# ppc_ddr2_1.net
KiCad netlist of a schematic drawn in Altium Designer
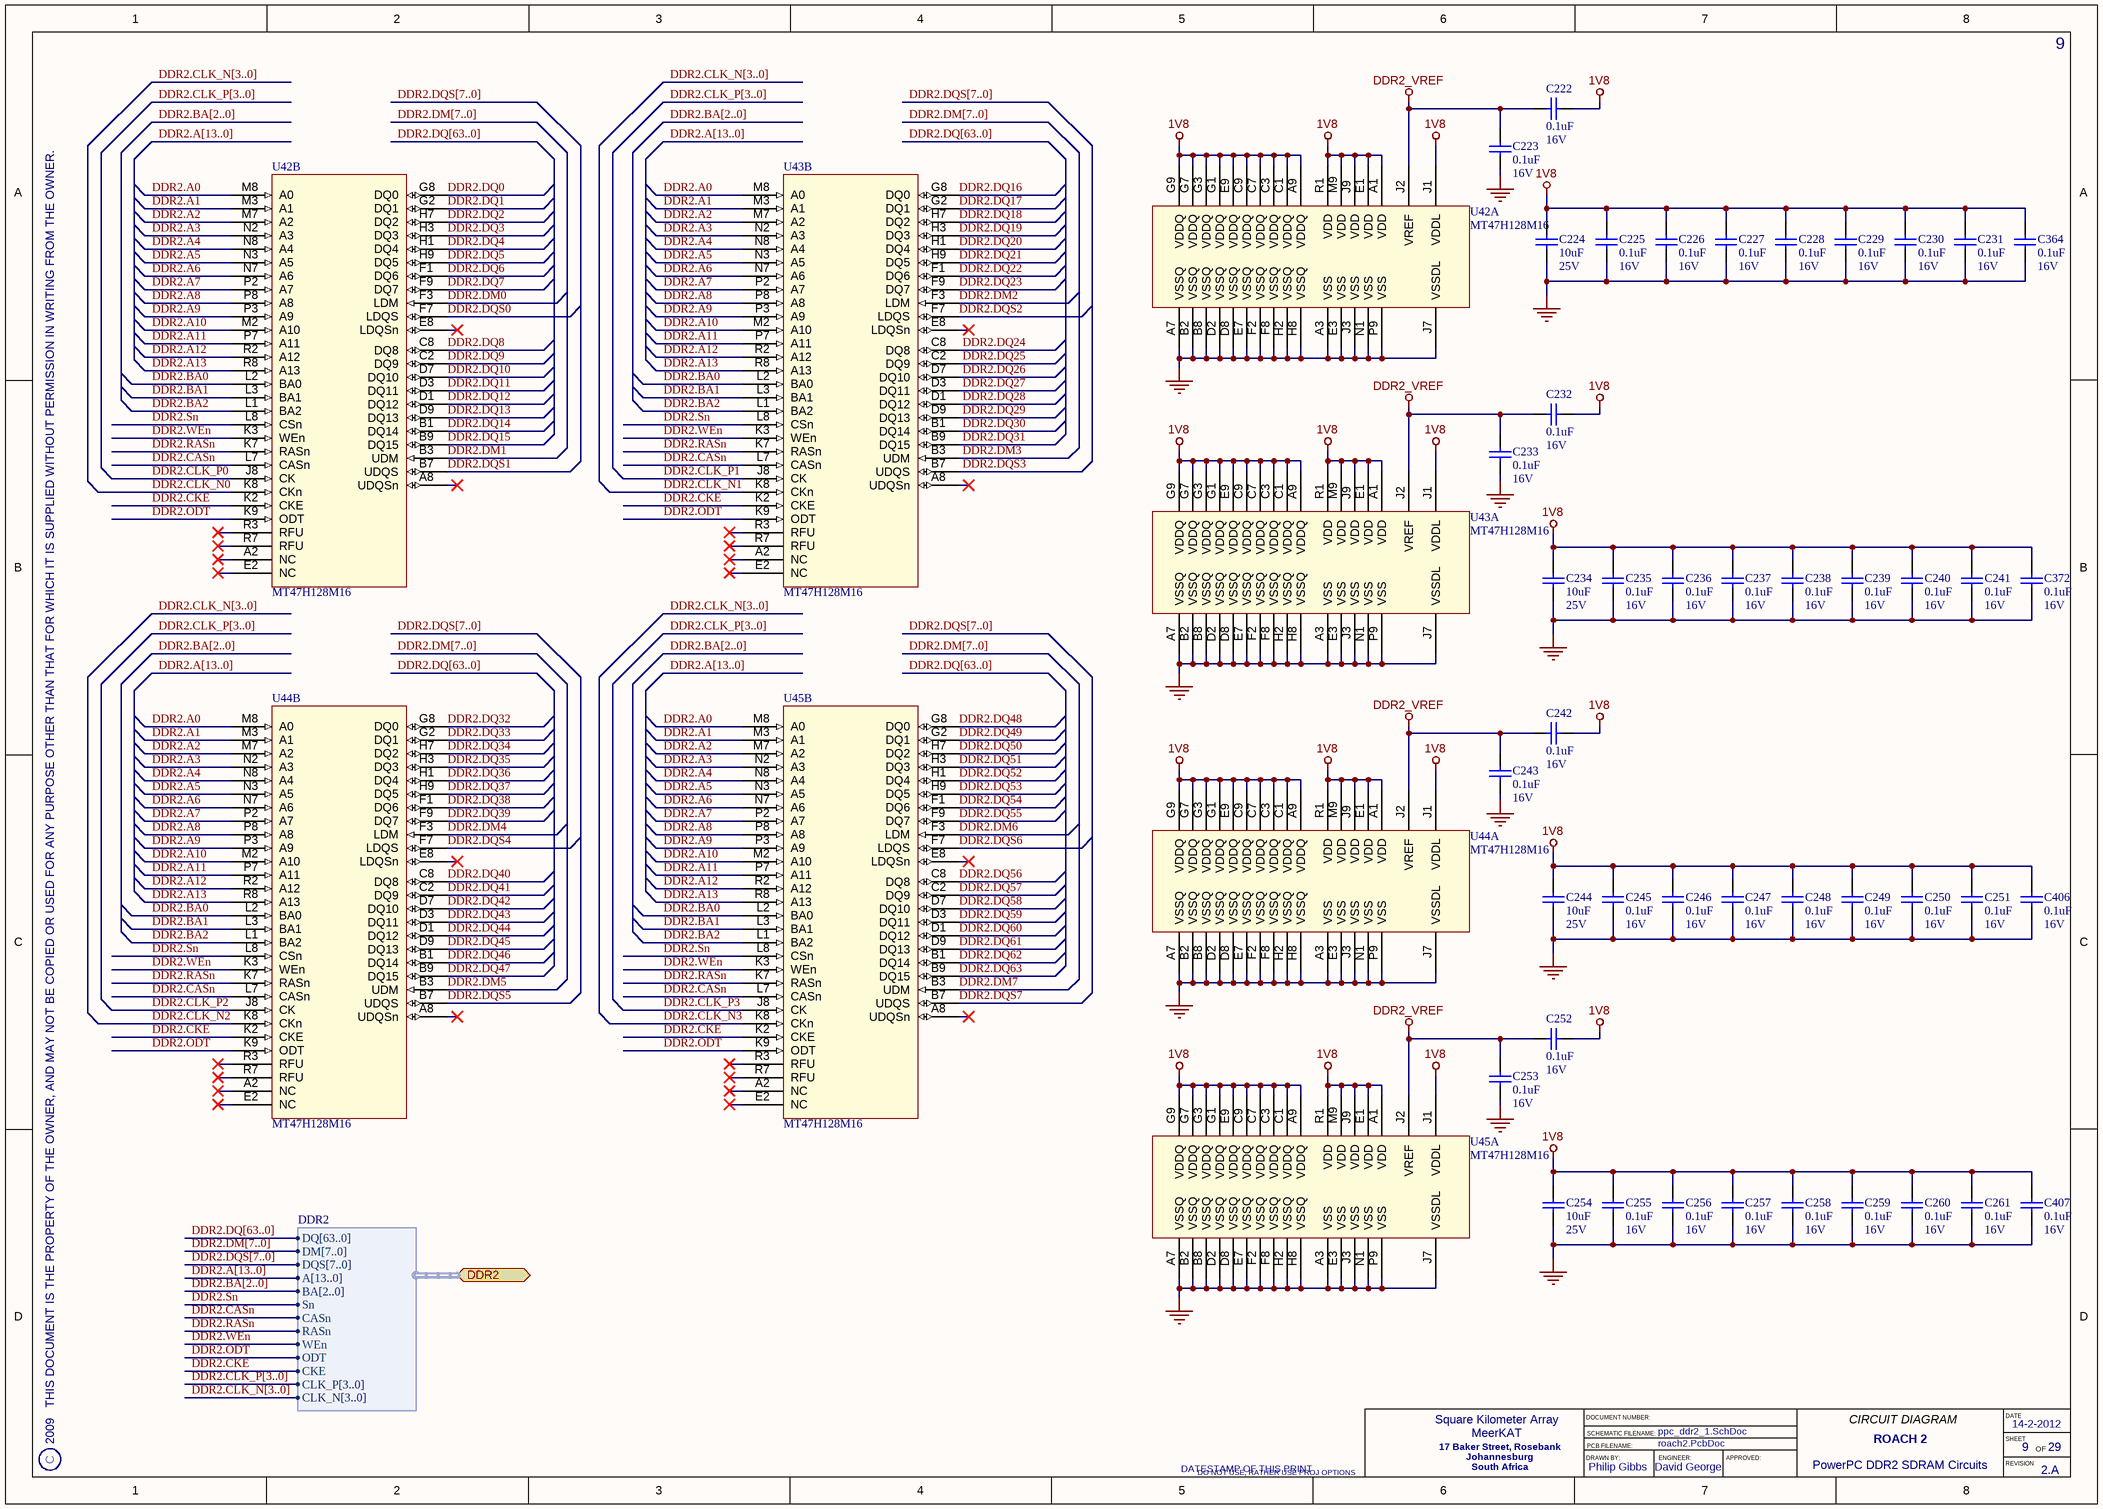
[diagram p0: ppc_ddr2_1.SchDoc]

(export (version "E")
  (design (tool "Eeschema 10.0.6"))
  (components
    (comp (ref "C222")
      (value "0.1uF")
      (footprint "CAPC1005X60L")
      (description "0.1uF, Ceramic Capacitor")
      (fields
        (field (name "RATING") "16V")
        (field (name "MANUFACTURER") "VENKEL")
        (field (name "PARTNUM") "C0402X7R160-104KN")
      )
      (libsource (lib "altium_db") (part "CapStd"))
    )
    (comp (ref "C223")
      (value "0.1uF")
      (footprint "CAPC1005X60L")
      (description "0.1uF, Ceramic Capacitor")
      (fields
        (field (name "RATING") "16V")
        (field (name "MANUFACTURER") "VENKEL")
        (field (name "PARTNUM") "C0402X7R160-104KN")
      )
      (libsource (lib "altium_db") (part "CapStd"))
    )
    (comp (ref "C224")
      (value "10uF")
      (footprint "CAPC3225X200L")
      (description "10uF, Ceramic Capacitor")
      (fields
        (field (name "RATING") "25V")
        (field (name "MANUFACTURER") "MURATA")
        (field (name "PARTNUM") "GRM32DR61E106KA12L")
      )
      (libsource (lib "altium_db") (part "CapStd"))
    )
    (comp (ref "C225")
      (value "0.1uF")
      (footprint "CAPC1005X60L")
      (description "0.1uF, Ceramic Capacitor")
      (fields
        (field (name "RATING") "16V")
        (field (name "MANUFACTURER") "VENKEL")
        (field (name "PARTNUM") "C0402X7R160-104KN")
      )
      (libsource (lib "altium_db") (part "CapStd"))
    )
    (comp (ref "C226")
      (value "0.1uF")
      (footprint "CAPC1005X60L")
      (description "0.1uF, Ceramic Capacitor")
      (fields
        (field (name "RATING") "16V")
        (field (name "MANUFACTURER") "VENKEL")
        (field (name "PARTNUM") "C0402X7R160-104KN")
      )
      (libsource (lib "altium_db") (part "CapStd"))
    )
    (comp (ref "C227")
      (value "0.1uF")
      (footprint "CAPC1005X60L")
      (description "0.1uF, Ceramic Capacitor")
      (fields
        (field (name "RATING") "16V")
        (field (name "MANUFACTURER") "VENKEL")
        (field (name "PARTNUM") "C0402X7R160-104KN")
      )
      (libsource (lib "altium_db") (part "CapStd"))
    )
    (comp (ref "C228")
      (value "0.1uF")
      (footprint "CAPC1005X60L")
      (description "0.1uF, Ceramic Capacitor")
      (fields
        (field (name "RATING") "16V")
        (field (name "MANUFACTURER") "VENKEL")
        (field (name "PARTNUM") "C0402X7R160-104KN")
      )
      (libsource (lib "altium_db") (part "CapStd"))
    )
    (comp (ref "C229")
      (value "0.1uF")
      (footprint "CAPC1005X60L")
      (description "0.1uF, Ceramic Capacitor")
      (fields
        (field (name "RATING") "16V")
        (field (name "MANUFACTURER") "VENKEL")
        (field (name "PARTNUM") "C0402X7R160-104KN")
      )
      (libsource (lib "altium_db") (part "CapStd"))
    )
    (comp (ref "C230")
      (value "0.1uF")
      (footprint "CAPC1005X60L")
      (description "0.1uF, Ceramic Capacitor")
      (fields
        (field (name "RATING") "16V")
        (field (name "MANUFACTURER") "VENKEL")
        (field (name "PARTNUM") "C0402X7R160-104KN")
      )
      (libsource (lib "altium_db") (part "CapStd"))
    )
    (comp (ref "C231")
      (value "0.1uF")
      (footprint "CAPC1005X60L")
      (description "0.1uF, Ceramic Capacitor")
      (fields
        (field (name "RATING") "16V")
        (field (name "MANUFACTURER") "VENKEL")
        (field (name "PARTNUM") "C0402X7R160-104KN")
      )
      (libsource (lib "altium_db") (part "CapStd"))
    )
    (comp (ref "C232")
      (value "0.1uF")
      (footprint "CAPC1005X60L")
      (description "0.1uF, Ceramic Capacitor")
      (fields
        (field (name "RATING") "16V")
        (field (name "MANUFACTURER") "VENKEL")
        (field (name "PARTNUM") "C0402X7R160-104KN")
      )
      (libsource (lib "altium_db") (part "CapStd"))
    )
    (comp (ref "C233")
      (value "0.1uF")
      (footprint "CAPC1005X60L")
      (description "0.1uF, Ceramic Capacitor")
      (fields
        (field (name "RATING") "16V")
        (field (name "MANUFACTURER") "VENKEL")
        (field (name "PARTNUM") "C0402X7R160-104KN")
      )
      (libsource (lib "altium_db") (part "CapStd"))
    )
    (comp (ref "C234")
      (value "10uF")
      (footprint "CAPC3225X200L")
      (description "10uF, Ceramic Capacitor")
      (fields
        (field (name "RATING") "25V")
        (field (name "MANUFACTURER") "MURATA")
        (field (name "PARTNUM") "GRM32DR61E106KA12L")
      )
      (libsource (lib "altium_db") (part "CapStd"))
    )
    (comp (ref "C235")
      (value "0.1uF")
      (footprint "CAPC1005X60L")
      (description "0.1uF, Ceramic Capacitor")
      (fields
        (field (name "RATING") "16V")
        (field (name "MANUFACTURER") "VENKEL")
        (field (name "PARTNUM") "C0402X7R160-104KN")
      )
      (libsource (lib "altium_db") (part "CapStd"))
    )
    (comp (ref "C236")
      (value "0.1uF")
      (footprint "CAPC1005X60L")
      (description "0.1uF, Ceramic Capacitor")
      (fields
        (field (name "RATING") "16V")
        (field (name "MANUFACTURER") "VENKEL")
        (field (name "PARTNUM") "C0402X7R160-104KN")
      )
      (libsource (lib "altium_db") (part "CapStd"))
    )
    (comp (ref "C237")
      (value "0.1uF")
      (footprint "CAPC1005X60L")
      (description "0.1uF, Ceramic Capacitor")
      (fields
        (field (name "RATING") "16V")
        (field (name "MANUFACTURER") "VENKEL")
        (field (name "PARTNUM") "C0402X7R160-104KN")
      )
      (libsource (lib "altium_db") (part "CapStd"))
    )
    (comp (ref "C238")
      (value "0.1uF")
      (footprint "CAPC1005X60L")
      (description "0.1uF, Ceramic Capacitor")
      (fields
        (field (name "RATING") "16V")
        (field (name "MANUFACTURER") "VENKEL")
        (field (name "PARTNUM") "C0402X7R160-104KN")
      )
      (libsource (lib "altium_db") (part "CapStd"))
    )
    (comp (ref "C239")
      (value "0.1uF")
      (footprint "CAPC1005X60L")
      (description "0.1uF, Ceramic Capacitor")
      (fields
        (field (name "RATING") "16V")
        (field (name "MANUFACTURER") "VENKEL")
        (field (name "PARTNUM") "C0402X7R160-104KN")
      )
      (libsource (lib "altium_db") (part "CapStd"))
    )
    (comp (ref "C240")
      (value "0.1uF")
      (footprint "CAPC1005X60L")
      (description "0.1uF, Ceramic Capacitor")
      (fields
        (field (name "RATING") "16V")
        (field (name "MANUFACTURER") "VENKEL")
        (field (name "PARTNUM") "C0402X7R160-104KN")
      )
      (libsource (lib "altium_db") (part "CapStd"))
    )
    (comp (ref "C241")
      (value "0.1uF")
      (footprint "CAPC1005X60L")
      (description "0.1uF, Ceramic Capacitor")
      (fields
        (field (name "RATING") "16V")
        (field (name "MANUFACTURER") "VENKEL")
        (field (name "PARTNUM") "C0402X7R160-104KN")
      )
      (libsource (lib "altium_db") (part "CapStd"))
    )
    (comp (ref "C242")
      (value "0.1uF")
      (footprint "CAPC1005X60L")
      (description "0.1uF, Ceramic Capacitor")
      (fields
        (field (name "RATING") "16V")
        (field (name "MANUFACTURER") "VENKEL")
        (field (name "PARTNUM") "C0402X7R160-104KN")
      )
      (libsource (lib "altium_db") (part "CapStd"))
    )
    (comp (ref "C243")
      (value "0.1uF")
      (footprint "CAPC1005X60L")
      (description "0.1uF, Ceramic Capacitor")
      (fields
        (field (name "RATING") "16V")
        (field (name "MANUFACTURER") "VENKEL")
        (field (name "PARTNUM") "C0402X7R160-104KN")
      )
      (libsource (lib "altium_db") (part "CapStd"))
    )
    (comp (ref "C244")
      (value "10uF")
      (footprint "CAPC3225X200L")
      (description "10uF, Ceramic Capacitor")
      (fields
        (field (name "RATING") "25V")
        (field (name "MANUFACTURER") "MURATA")
        (field (name "PARTNUM") "GRM32DR61E106KA12L")
      )
      (libsource (lib "altium_db") (part "CapStd"))
    )
    (comp (ref "C245")
      (value "0.1uF")
      (footprint "CAPC1005X60L")
      (description "0.1uF, Ceramic Capacitor")
      (fields
        (field (name "RATING") "16V")
        (field (name "MANUFACTURER") "VENKEL")
        (field (name "PARTNUM") "C0402X7R160-104KN")
      )
      (libsource (lib "altium_db") (part "CapStd"))
    )
    (comp (ref "C246")
      (value "0.1uF")
      (footprint "CAPC1005X60L")
      (description "0.1uF, Ceramic Capacitor")
      (fields
        (field (name "RATING") "16V")
        (field (name "MANUFACTURER") "VENKEL")
        (field (name "PARTNUM") "C0402X7R160-104KN")
      )
      (libsource (lib "altium_db") (part "CapStd"))
    )
    (comp (ref "C247")
      (value "0.1uF")
      (footprint "CAPC1005X60L")
      (description "0.1uF, Ceramic Capacitor")
      (fields
        (field (name "RATING") "16V")
        (field (name "MANUFACTURER") "VENKEL")
        (field (name "PARTNUM") "C0402X7R160-104KN")
      )
      (libsource (lib "altium_db") (part "CapStd"))
    )
    (comp (ref "C248")
      (value "0.1uF")
      (footprint "CAPC1005X60L")
      (description "0.1uF, Ceramic Capacitor")
      (fields
        (field (name "RATING") "16V")
        (field (name "MANUFACTURER") "VENKEL")
        (field (name "PARTNUM") "C0402X7R160-104KN")
      )
      (libsource (lib "altium_db") (part "CapStd"))
    )
    (comp (ref "C249")
      (value "0.1uF")
      (footprint "CAPC1005X60L")
      (description "0.1uF, Ceramic Capacitor")
      (fields
        (field (name "RATING") "16V")
        (field (name "MANUFACTURER") "VENKEL")
        (field (name "PARTNUM") "C0402X7R160-104KN")
      )
      (libsource (lib "altium_db") (part "CapStd"))
    )
    (comp (ref "C250")
      (value "0.1uF")
      (footprint "CAPC1005X60L")
      (description "0.1uF, Ceramic Capacitor")
      (fields
        (field (name "RATING") "16V")
        (field (name "MANUFACTURER") "VENKEL")
        (field (name "PARTNUM") "C0402X7R160-104KN")
      )
      (libsource (lib "altium_db") (part "CapStd"))
    )
    (comp (ref "C251")
      (value "0.1uF")
      (footprint "CAPC1005X60L")
      (description "0.1uF, Ceramic Capacitor")
      (fields
        (field (name "RATING") "16V")
        (field (name "MANUFACTURER") "VENKEL")
        (field (name "PARTNUM") "C0402X7R160-104KN")
      )
      (libsource (lib "altium_db") (part "CapStd"))
    )
    (comp (ref "C252")
      (value "0.1uF")
      (footprint "CAPC1005X60L")
      (description "0.1uF, Ceramic Capacitor")
      (fields
        (field (name "RATING") "16V")
        (field (name "MANUFACTURER") "VENKEL")
        (field (name "PARTNUM") "C0402X7R160-104KN")
      )
      (libsource (lib "altium_db") (part "CapStd"))
    )
    (comp (ref "C253")
      (value "0.1uF")
      (footprint "CAPC1005X60L")
      (description "0.1uF, Ceramic Capacitor")
      (fields
        (field (name "RATING") "16V")
        (field (name "MANUFACTURER") "VENKEL")
        (field (name "PARTNUM") "C0402X7R160-104KN")
      )
      (libsource (lib "altium_db") (part "CapStd"))
    )
    (comp (ref "C254")
      (value "10uF")
      (footprint "CAPC3225X200L")
      (description "10uF, Ceramic Capacitor")
      (fields
        (field (name "RATING") "25V")
        (field (name "MANUFACTURER") "MURATA")
        (field (name "PARTNUM") "GRM32DR61E106KA12L")
      )
      (libsource (lib "altium_db") (part "CapStd"))
    )
    (comp (ref "C255")
      (value "0.1uF")
      (footprint "CAPC1005X60L")
      (description "0.1uF, Ceramic Capacitor")
      (fields
        (field (name "RATING") "16V")
        (field (name "MANUFACTURER") "VENKEL")
        (field (name "PARTNUM") "C0402X7R160-104KN")
      )
      (libsource (lib "altium_db") (part "CapStd"))
    )
    (comp (ref "C256")
      (value "0.1uF")
      (footprint "CAPC1005X60L")
      (description "0.1uF, Ceramic Capacitor")
      (fields
        (field (name "RATING") "16V")
        (field (name "MANUFACTURER") "VENKEL")
        (field (name "PARTNUM") "C0402X7R160-104KN")
      )
      (libsource (lib "altium_db") (part "CapStd"))
    )
    (comp (ref "C257")
      (value "0.1uF")
      (footprint "CAPC1005X60L")
      (description "0.1uF, Ceramic Capacitor")
      (fields
        (field (name "RATING") "16V")
        (field (name "MANUFACTURER") "VENKEL")
        (field (name "PARTNUM") "C0402X7R160-104KN")
      )
      (libsource (lib "altium_db") (part "CapStd"))
    )
    (comp (ref "C258")
      (value "0.1uF")
      (footprint "CAPC1005X60L")
      (description "0.1uF, Ceramic Capacitor")
      (fields
        (field (name "RATING") "16V")
        (field (name "MANUFACTURER") "VENKEL")
        (field (name "PARTNUM") "C0402X7R160-104KN")
      )
      (libsource (lib "altium_db") (part "CapStd"))
    )
    (comp (ref "C259")
      (value "0.1uF")
      (footprint "CAPC1005X60L")
      (description "0.1uF, Ceramic Capacitor")
      (fields
        (field (name "RATING") "16V")
        (field (name "MANUFACTURER") "VENKEL")
        (field (name "PARTNUM") "C0402X7R160-104KN")
      )
      (libsource (lib "altium_db") (part "CapStd"))
    )
    (comp (ref "C260")
      (value "0.1uF")
      (footprint "CAPC1005X60L")
      (description "0.1uF, Ceramic Capacitor")
      (fields
        (field (name "RATING") "16V")
        (field (name "MANUFACTURER") "VENKEL")
        (field (name "PARTNUM") "C0402X7R160-104KN")
      )
      (libsource (lib "altium_db") (part "CapStd"))
    )
    (comp (ref "C261")
      (value "0.1uF")
      (footprint "CAPC1005X60L")
      (description "0.1uF, Ceramic Capacitor")
      (fields
        (field (name "RATING") "16V")
        (field (name "MANUFACTURER") "VENKEL")
        (field (name "PARTNUM") "C0402X7R160-104KN")
      )
      (libsource (lib "altium_db") (part "CapStd"))
    )
    (comp (ref "C364")
      (value "0.1uF")
      (footprint "CAPC1005X60L")
      (description "0.1uF, Ceramic Capacitor")
      (fields
        (field (name "RATING") "16V")
        (field (name "MANUFACTURER") "VENKEL")
        (field (name "PARTNUM") "C0402X7R160-104KN")
      )
      (libsource (lib "altium_db") (part "CapStd"))
    )
    (comp (ref "C372")
      (value "0.1uF")
      (footprint "CAPC1005X60L")
      (description "0.1uF, Ceramic Capacitor")
      (fields
        (field (name "RATING") "16V")
        (field (name "MANUFACTURER") "VENKEL")
        (field (name "PARTNUM") "C0402X7R160-104KN")
      )
      (libsource (lib "altium_db") (part "CapStd"))
    )
    (comp (ref "C406")
      (value "0.1uF")
      (footprint "CAPC1005X60L")
      (description "0.1uF, Ceramic Capacitor")
      (fields
        (field (name "RATING") "16V")
        (field (name "MANUFACTURER") "VENKEL")
        (field (name "PARTNUM") "C0402X7R160-104KN")
      )
      (libsource (lib "altium_db") (part "CapStd"))
    )
    (comp (ref "C407")
      (value "0.1uF")
      (footprint "CAPC1005X60L")
      (description "0.1uF, Ceramic Capacitor")
      (fields
        (field (name "RATING") "16V")
        (field (name "MANUFACTURER") "VENKEL")
        (field (name "PARTNUM") "C0402X7R160-104KN")
      )
      (libsource (lib "altium_db") (part "CapStd"))
    )
    (comp (ref "U42")
      (value "MT47H128M16")
      (footprint "DDR2_BGA84")
      (description "2Gb, x16, BGA84 DDR2 SDRAM IC")
      (fields (field (name "MANUFACTURER") "Micron"))
      (libsource (lib "altium_db") (part "MT47H128M16"))
    )
    (comp (ref "U43")
      (value "MT47H128M16")
      (footprint "DDR2_BGA84")
      (description "2Gb, x16, BGA84 DDR2 SDRAM IC")
      (fields (field (name "MANUFACTURER") "Micron"))
      (libsource (lib "altium_db") (part "MT47H128M16"))
    )
    (comp (ref "U44")
      (value "MT47H128M16")
      (footprint "DDR2_BGA84")
      (description "2Gb, x16, BGA84 DDR2 SDRAM IC")
      (fields (field (name "MANUFACTURER") "Micron"))
      (libsource (lib "altium_db") (part "MT47H128M16"))
    )
    (comp (ref "U45")
      (value "MT47H128M16")
      (footprint "DDR2_BGA84")
      (description "2Gb, x16, BGA84 DDR2 SDRAM IC")
      (fields (field (name "MANUFACTURER") "Micron"))
      (libsource (lib "altium_db") (part "MT47H128M16"))
    )
  )
  (nets
    (net (code "2") (name "/DDR2.A0") (class "Default")
      (node (ref "U42") (pin "M8") (pinfunction "A0_M8") (pintype "input"))
      (node (ref "U43") (pin "M8") (pinfunction "A0_M8") (pintype "input"))
      (node (ref "U44") (pin "M8") (pinfunction "A0_M8") (pintype "input"))
      (node (ref "U45") (pin "M8") (pinfunction "A0_M8") (pintype "input"))
    )
    (net (code "3") (name "/DDR2.A1") (class "Default")
      (node (ref "U42") (pin "M3") (pinfunction "A1_M3") (pintype "input"))
      (node (ref "U43") (pin "M3") (pinfunction "A1_M3") (pintype "input"))
      (node (ref "U44") (pin "M3") (pinfunction "A1_M3") (pintype "input"))
      (node (ref "U45") (pin "M3") (pinfunction "A1_M3") (pintype "input"))
    )
    (net (code "4") (name "/DDR2.A2") (class "Default")
      (node (ref "U42") (pin "M7") (pinfunction "A2_M7") (pintype "input"))
      (node (ref "U43") (pin "M7") (pinfunction "A2_M7") (pintype "input"))
      (node (ref "U44") (pin "M7") (pinfunction "A2_M7") (pintype "input"))
      (node (ref "U45") (pin "M7") (pinfunction "A2_M7") (pintype "input"))
    )
    (net (code "5") (name "/DDR2.A3") (class "Default")
      (node (ref "U42") (pin "N2") (pinfunction "A3_N2") (pintype "input"))
      (node (ref "U43") (pin "N2") (pinfunction "A3_N2") (pintype "input"))
      (node (ref "U44") (pin "N2") (pinfunction "A3_N2") (pintype "input"))
      (node (ref "U45") (pin "N2") (pinfunction "A3_N2") (pintype "input"))
    )
    (net (code "6") (name "/DDR2.A4") (class "Default")
      (node (ref "U42") (pin "N8") (pinfunction "A4_N8") (pintype "input"))
      (node (ref "U43") (pin "N8") (pinfunction "A4_N8") (pintype "input"))
      (node (ref "U44") (pin "N8") (pinfunction "A4_N8") (pintype "input"))
      (node (ref "U45") (pin "N8") (pinfunction "A4_N8") (pintype "input"))
    )
    (net (code "7") (name "/DDR2.A5") (class "Default")
      (node (ref "U42") (pin "N3") (pinfunction "A5_N3") (pintype "input"))
      (node (ref "U43") (pin "N3") (pinfunction "A5_N3") (pintype "input"))
      (node (ref "U44") (pin "N3") (pinfunction "A5_N3") (pintype "input"))
      (node (ref "U45") (pin "N3") (pinfunction "A5_N3") (pintype "input"))
    )
    (net (code "8") (name "/DDR2.A6") (class "Default")
      (node (ref "U42") (pin "N7") (pinfunction "A6_N7") (pintype "input"))
      (node (ref "U43") (pin "N7") (pinfunction "A6_N7") (pintype "input"))
      (node (ref "U44") (pin "N7") (pinfunction "A6_N7") (pintype "input"))
      (node (ref "U45") (pin "N7") (pinfunction "A6_N7") (pintype "input"))
    )
    (net (code "9") (name "/DDR2.A7") (class "Default")
      (node (ref "U42") (pin "P2") (pinfunction "A7_P2") (pintype "input"))
      (node (ref "U43") (pin "P2") (pinfunction "A7_P2") (pintype "input"))
      (node (ref "U44") (pin "P2") (pinfunction "A7_P2") (pintype "input"))
      (node (ref "U45") (pin "P2") (pinfunction "A7_P2") (pintype "input"))
    )
    (net (code "10") (name "/DDR2.A8") (class "Default")
      (node (ref "U42") (pin "P8") (pinfunction "A8_P8") (pintype "input"))
      (node (ref "U43") (pin "P8") (pinfunction "A8_P8") (pintype "input"))
      (node (ref "U44") (pin "P8") (pinfunction "A8_P8") (pintype "input"))
      (node (ref "U45") (pin "P8") (pinfunction "A8_P8") (pintype "input"))
    )
    (net (code "11") (name "/DDR2.A9") (class "Default")
      (node (ref "U42") (pin "P3") (pinfunction "A9_P3") (pintype "input"))
      (node (ref "U43") (pin "P3") (pinfunction "A9_P3") (pintype "input"))
      (node (ref "U44") (pin "P3") (pinfunction "A9_P3") (pintype "input"))
      (node (ref "U45") (pin "P3") (pinfunction "A9_P3") (pintype "input"))
    )
    (net (code "12") (name "/DDR2.A10") (class "Default")
      (node (ref "U42") (pin "M2") (pinfunction "A10_M2") (pintype "input"))
      (node (ref "U43") (pin "M2") (pinfunction "A10_M2") (pintype "input"))
      (node (ref "U44") (pin "M2") (pinfunction "A10_M2") (pintype "input"))
      (node (ref "U45") (pin "M2") (pinfunction "A10_M2") (pintype "input"))
    )
    (net (code "13") (name "/DDR2.A11") (class "Default")
      (node (ref "U42") (pin "P7") (pinfunction "A11_P7") (pintype "input"))
      (node (ref "U43") (pin "P7") (pinfunction "A11_P7") (pintype "input"))
      (node (ref "U44") (pin "P7") (pinfunction "A11_P7") (pintype "input"))
      (node (ref "U45") (pin "P7") (pinfunction "A11_P7") (pintype "input"))
    )
    (net (code "14") (name "/DDR2.A12") (class "Default")
      (node (ref "U42") (pin "R2") (pinfunction "A12_R2") (pintype "input"))
      (node (ref "U43") (pin "R2") (pinfunction "A12_R2") (pintype "input"))
      (node (ref "U44") (pin "R2") (pinfunction "A12_R2") (pintype "input"))
      (node (ref "U45") (pin "R2") (pinfunction "A12_R2") (pintype "input"))
    )
    (net (code "15") (name "/DDR2.A13") (class "Default")
      (node (ref "U42") (pin "R8") (pinfunction "A13_R8") (pintype "input"))
      (node (ref "U43") (pin "R8") (pinfunction "A13_R8") (pintype "input"))
      (node (ref "U44") (pin "R8") (pinfunction "A13_R8") (pintype "input"))
      (node (ref "U45") (pin "R8") (pinfunction "A13_R8") (pintype "input"))
    )
    (net (code "17") (name "/DDR2.BA0") (class "Default")
      (node (ref "U42") (pin "L2") (pinfunction "BA0_L2") (pintype "input"))
      (node (ref "U43") (pin "L2") (pinfunction "BA0_L2") (pintype "input"))
      (node (ref "U44") (pin "L2") (pinfunction "BA0_L2") (pintype "input"))
      (node (ref "U45") (pin "L2") (pinfunction "BA0_L2") (pintype "input"))
    )
    (net (code "18") (name "/DDR2.BA1") (class "Default")
      (node (ref "U42") (pin "L3") (pinfunction "BA1_L3") (pintype "input"))
      (node (ref "U43") (pin "L3") (pinfunction "BA1_L3") (pintype "input"))
      (node (ref "U44") (pin "L3") (pinfunction "BA1_L3") (pintype "input"))
      (node (ref "U45") (pin "L3") (pinfunction "BA1_L3") (pintype "input"))
    )
    (net (code "19") (name "/DDR2.BA2") (class "Default")
      (node (ref "U42") (pin "L1") (pinfunction "BA2_L1") (pintype "input"))
      (node (ref "U43") (pin "L1") (pinfunction "BA2_L1") (pintype "input"))
      (node (ref "U44") (pin "L1") (pinfunction "BA2_L1") (pintype "input"))
      (node (ref "U45") (pin "L1") (pinfunction "BA2_L1") (pintype "input"))
    )
    (net (code "21") (name "/DDR2.CASn") (class "Default")
      (node (ref "U42") (pin "L7") (pinfunction "CASn_L7") (pintype "input"))
      (node (ref "U43") (pin "L7") (pinfunction "CASn_L7") (pintype "input"))
      (node (ref "U44") (pin "L7") (pinfunction "CASn_L7") (pintype "input"))
      (node (ref "U45") (pin "L7") (pinfunction "CASn_L7") (pintype "input"))
    )
    (net (code "22") (name "/DDR2.CKE") (class "Default")
      (node (ref "U42") (pin "K2") (pinfunction "CKE_K2") (pintype "input"))
      (node (ref "U43") (pin "K2") (pinfunction "CKE_K2") (pintype "input"))
      (node (ref "U44") (pin "K2") (pinfunction "CKE_K2") (pintype "input"))
      (node (ref "U45") (pin "K2") (pinfunction "CKE_K2") (pintype "input"))
    )
    (net (code "23") (name "/DDR2.CLK_N0") (class "Default")
      (node (ref "U42") (pin "K8") (pinfunction "CKn_K8") (pintype "input"))
    )
    (net (code "24") (name "/DDR2.CLK_N1") (class "Default")
      (node (ref "U43") (pin "K8") (pinfunction "CKn_K8") (pintype "input"))
    )
    (net (code "25") (name "/DDR2.CLK_N2") (class "Default")
      (node (ref "U44") (pin "K8") (pinfunction "CKn_K8") (pintype "input"))
    )
    (net (code "26") (name "/DDR2.CLK_N3") (class "Default")
      (node (ref "U45") (pin "K8") (pinfunction "CKn_K8") (pintype "input"))
    )
    (net (code "28") (name "/DDR2.CLK_P0") (class "Default")
      (node (ref "U42") (pin "J8") (pinfunction "CK_J8") (pintype "input"))
    )
    (net (code "29") (name "/DDR2.CLK_P1") (class "Default")
      (node (ref "U43") (pin "J8") (pinfunction "CK_J8") (pintype "input"))
    )
    (net (code "30") (name "/DDR2.CLK_P2") (class "Default")
      (node (ref "U44") (pin "J8") (pinfunction "CK_J8") (pintype "input"))
    )
    (net (code "31") (name "/DDR2.CLK_P3") (class "Default")
      (node (ref "U45") (pin "J8") (pinfunction "CK_J8") (pintype "input"))
    )
    (net (code "33") (name "/DDR2.DM0") (class "Default")
      (node (ref "U42") (pin "F3") (pinfunction "LDM_F3") (pintype "input"))
    )
    (net (code "34") (name "/DDR2.DM1") (class "Default")
      (node (ref "U42") (pin "B3") (pinfunction "UDM_B3") (pintype "input"))
    )
    (net (code "35") (name "/DDR2.DM2") (class "Default")
      (node (ref "U43") (pin "F3") (pinfunction "LDM_F3") (pintype "input"))
    )
    (net (code "36") (name "/DDR2.DM3") (class "Default")
      (node (ref "U43") (pin "B3") (pinfunction "UDM_B3") (pintype "input"))
    )
    (net (code "37") (name "/DDR2.DM4") (class "Default")
      (node (ref "U44") (pin "F3") (pinfunction "LDM_F3") (pintype "input"))
    )
    (net (code "38") (name "/DDR2.DM5") (class "Default")
      (node (ref "U44") (pin "B3") (pinfunction "UDM_B3") (pintype "input"))
    )
    (net (code "39") (name "/DDR2.DM6") (class "Default")
      (node (ref "U45") (pin "F3") (pinfunction "LDM_F3") (pintype "input"))
    )
    (net (code "40") (name "/DDR2.DM7") (class "Default")
      (node (ref "U45") (pin "B3") (pinfunction "UDM_B3") (pintype "input"))
    )
    (net (code "42") (name "/DDR2.DQ0") (class "Default")
      (node (ref "U42") (pin "G8") (pinfunction "DQ0_G8") (pintype "bidirectional"))
    )
    (net (code "43") (name "/DDR2.DQ1") (class "Default")
      (node (ref "U42") (pin "G2") (pinfunction "DQ1_G2") (pintype "bidirectional"))
    )
    (net (code "44") (name "/DDR2.DQ2") (class "Default")
      (node (ref "U42") (pin "H7") (pinfunction "DQ2_H7") (pintype "bidirectional"))
    )
    (net (code "45") (name "/DDR2.DQ3") (class "Default")
      (node (ref "U42") (pin "H3") (pinfunction "DQ3_H3") (pintype "bidirectional"))
    )
    (net (code "46") (name "/DDR2.DQ4") (class "Default")
      (node (ref "U42") (pin "H1") (pinfunction "DQ4_H1") (pintype "bidirectional"))
    )
    (net (code "47") (name "/DDR2.DQ5") (class "Default")
      (node (ref "U42") (pin "H9") (pinfunction "DQ5_H9") (pintype "bidirectional"))
    )
    (net (code "48") (name "/DDR2.DQ6") (class "Default")
      (node (ref "U42") (pin "F1") (pinfunction "DQ6_F1") (pintype "bidirectional"))
    )
    (net (code "49") (name "/DDR2.DQ7") (class "Default")
      (node (ref "U42") (pin "F9") (pinfunction "DQ7_F9") (pintype "bidirectional"))
    )
    (net (code "50") (name "/DDR2.DQ8") (class "Default")
      (node (ref "U42") (pin "C8") (pinfunction "DQ8_C8") (pintype "bidirectional"))
    )
    (net (code "51") (name "/DDR2.DQ9") (class "Default")
      (node (ref "U42") (pin "C2") (pinfunction "DQ9_C2") (pintype "bidirectional"))
    )
    (net (code "52") (name "/DDR2.DQ10") (class "Default")
      (node (ref "U42") (pin "D7") (pinfunction "DQ10_D7") (pintype "bidirectional"))
    )
    (net (code "53") (name "/DDR2.DQ11") (class "Default")
      (node (ref "U42") (pin "D3") (pinfunction "DQ11_D3") (pintype "bidirectional"))
    )
    (net (code "54") (name "/DDR2.DQ12") (class "Default")
      (node (ref "U42") (pin "D1") (pinfunction "DQ12_D1") (pintype "bidirectional"))
    )
    (net (code "55") (name "/DDR2.DQ13") (class "Default")
      (node (ref "U42") (pin "D9") (pinfunction "DQ13_D9") (pintype "bidirectional"))
    )
    (net (code "56") (name "/DDR2.DQ14") (class "Default")
      (node (ref "U42") (pin "B1") (pinfunction "DQ14_B1") (pintype "bidirectional"))
    )
    (net (code "57") (name "/DDR2.DQ15") (class "Default")
      (node (ref "U42") (pin "B9") (pinfunction "DQ15_B9") (pintype "bidirectional"))
    )
    (net (code "58") (name "/DDR2.DQ16") (class "Default")
      (node (ref "U43") (pin "G8") (pinfunction "DQ0_G8") (pintype "bidirectional"))
    )
    (net (code "59") (name "/DDR2.DQ17") (class "Default")
      (node (ref "U43") (pin "G2") (pinfunction "DQ1_G2") (pintype "bidirectional"))
    )
    (net (code "60") (name "/DDR2.DQ18") (class "Default")
      (node (ref "U43") (pin "H7") (pinfunction "DQ2_H7") (pintype "bidirectional"))
    )
    (net (code "61") (name "/DDR2.DQ19") (class "Default")
      (node (ref "U43") (pin "H3") (pinfunction "DQ3_H3") (pintype "bidirectional"))
    )
    (net (code "62") (name "/DDR2.DQ20") (class "Default")
      (node (ref "U43") (pin "H1") (pinfunction "DQ4_H1") (pintype "bidirectional"))
    )
    (net (code "63") (name "/DDR2.DQ21") (class "Default")
      (node (ref "U43") (pin "H9") (pinfunction "DQ5_H9") (pintype "bidirectional"))
    )
    (net (code "64") (name "/DDR2.DQ22") (class "Default")
      (node (ref "U43") (pin "F1") (pinfunction "DQ6_F1") (pintype "bidirectional"))
    )
    (net (code "65") (name "/DDR2.DQ23") (class "Default")
      (node (ref "U43") (pin "F9") (pinfunction "DQ7_F9") (pintype "bidirectional"))
    )
    (net (code "66") (name "/DDR2.DQ24") (class "Default")
      (node (ref "U43") (pin "C8") (pinfunction "DQ8_C8") (pintype "bidirectional"))
    )
    (net (code "67") (name "/DDR2.DQ25") (class "Default")
      (node (ref "U43") (pin "C2") (pinfunction "DQ9_C2") (pintype "bidirectional"))
    )
    (net (code "68") (name "/DDR2.DQ26") (class "Default")
      (node (ref "U43") (pin "D7") (pinfunction "DQ10_D7") (pintype "bidirectional"))
    )
    (net (code "69") (name "/DDR2.DQ27") (class "Default")
      (node (ref "U43") (pin "D3") (pinfunction "DQ11_D3") (pintype "bidirectional"))
    )
    (net (code "70") (name "/DDR2.DQ28") (class "Default")
      (node (ref "U43") (pin "D1") (pinfunction "DQ12_D1") (pintype "bidirectional"))
    )
    (net (code "71") (name "/DDR2.DQ29") (class "Default")
      (node (ref "U43") (pin "D9") (pinfunction "DQ13_D9") (pintype "bidirectional"))
    )
    (net (code "72") (name "/DDR2.DQ30") (class "Default")
      (node (ref "U43") (pin "B1") (pinfunction "DQ14_B1") (pintype "bidirectional"))
    )
    (net (code "73") (name "/DDR2.DQ31") (class "Default")
      (node (ref "U43") (pin "B9") (pinfunction "DQ15_B9") (pintype "bidirectional"))
    )
    (net (code "74") (name "/DDR2.DQ32") (class "Default")
      (node (ref "U44") (pin "G8") (pinfunction "DQ0_G8") (pintype "bidirectional"))
    )
    (net (code "75") (name "/DDR2.DQ33") (class "Default")
      (node (ref "U44") (pin "G2") (pinfunction "DQ1_G2") (pintype "bidirectional"))
    )
    (net (code "76") (name "/DDR2.DQ34") (class "Default")
      (node (ref "U44") (pin "H7") (pinfunction "DQ2_H7") (pintype "bidirectional"))
    )
    (net (code "77") (name "/DDR2.DQ35") (class "Default")
      (node (ref "U44") (pin "H3") (pinfunction "DQ3_H3") (pintype "bidirectional"))
    )
    (net (code "78") (name "/DDR2.DQ36") (class "Default")
      (node (ref "U44") (pin "H1") (pinfunction "DQ4_H1") (pintype "bidirectional"))
    )
    (net (code "79") (name "/DDR2.DQ37") (class "Default")
      (node (ref "U44") (pin "H9") (pinfunction "DQ5_H9") (pintype "bidirectional"))
    )
    (net (code "80") (name "/DDR2.DQ38") (class "Default")
      (node (ref "U44") (pin "F1") (pinfunction "DQ6_F1") (pintype "bidirectional"))
    )
    (net (code "81") (name "/DDR2.DQ39") (class "Default")
      (node (ref "U44") (pin "F9") (pinfunction "DQ7_F9") (pintype "bidirectional"))
    )
    (net (code "82") (name "/DDR2.DQ40") (class "Default")
      (node (ref "U44") (pin "C8") (pinfunction "DQ8_C8") (pintype "bidirectional"))
    )
    (net (code "83") (name "/DDR2.DQ41") (class "Default")
      (node (ref "U44") (pin "C2") (pinfunction "DQ9_C2") (pintype "bidirectional"))
    )
    (net (code "84") (name "/DDR2.DQ42") (class "Default")
      (node (ref "U44") (pin "D7") (pinfunction "DQ10_D7") (pintype "bidirectional"))
    )
    (net (code "85") (name "/DDR2.DQ43") (class "Default")
      (node (ref "U44") (pin "D3") (pinfunction "DQ11_D3") (pintype "bidirectional"))
    )
    (net (code "86") (name "/DDR2.DQ44") (class "Default")
      (node (ref "U44") (pin "D1") (pinfunction "DQ12_D1") (pintype "bidirectional"))
    )
    (net (code "87") (name "/DDR2.DQ45") (class "Default")
      (node (ref "U44") (pin "D9") (pinfunction "DQ13_D9") (pintype "bidirectional"))
    )
    (net (code "88") (name "/DDR2.DQ46") (class "Default")
      (node (ref "U44") (pin "B1") (pinfunction "DQ14_B1") (pintype "bidirectional"))
    )
    (net (code "89") (name "/DDR2.DQ47") (class "Default")
      (node (ref "U44") (pin "B9") (pinfunction "DQ15_B9") (pintype "bidirectional"))
    )
    (net (code "90") (name "/DDR2.DQ48") (class "Default")
      (node (ref "U45") (pin "G8") (pinfunction "DQ0_G8") (pintype "bidirectional"))
    )
    (net (code "91") (name "/DDR2.DQ49") (class "Default")
      (node (ref "U45") (pin "G2") (pinfunction "DQ1_G2") (pintype "bidirectional"))
    )
    (net (code "92") (name "/DDR2.DQ50") (class "Default")
      (node (ref "U45") (pin "H7") (pinfunction "DQ2_H7") (pintype "bidirectional"))
    )
    (net (code "93") (name "/DDR2.DQ51") (class "Default")
      (node (ref "U45") (pin "H3") (pinfunction "DQ3_H3") (pintype "bidirectional"))
    )
    (net (code "94") (name "/DDR2.DQ52") (class "Default")
      (node (ref "U45") (pin "H1") (pinfunction "DQ4_H1") (pintype "bidirectional"))
    )
    (net (code "95") (name "/DDR2.DQ53") (class "Default")
      (node (ref "U45") (pin "H9") (pinfunction "DQ5_H9") (pintype "bidirectional"))
    )
    (net (code "96") (name "/DDR2.DQ54") (class "Default")
      (node (ref "U45") (pin "F1") (pinfunction "DQ6_F1") (pintype "bidirectional"))
    )
    (net (code "97") (name "/DDR2.DQ55") (class "Default")
      (node (ref "U45") (pin "F9") (pinfunction "DQ7_F9") (pintype "bidirectional"))
    )
    (net (code "98") (name "/DDR2.DQ56") (class "Default")
      (node (ref "U45") (pin "C8") (pinfunction "DQ8_C8") (pintype "bidirectional"))
    )
    (net (code "99") (name "/DDR2.DQ57") (class "Default")
      (node (ref "U45") (pin "C2") (pinfunction "DQ9_C2") (pintype "bidirectional"))
    )
    (net (code "100") (name "/DDR2.DQ58") (class "Default")
      (node (ref "U45") (pin "D7") (pinfunction "DQ10_D7") (pintype "bidirectional"))
    )
    (net (code "101") (name "/DDR2.DQ59") (class "Default")
      (node (ref "U45") (pin "D3") (pinfunction "DQ11_D3") (pintype "bidirectional"))
    )
    (net (code "102") (name "/DDR2.DQ60") (class "Default")
      (node (ref "U45") (pin "D1") (pinfunction "DQ12_D1") (pintype "bidirectional"))
    )
    (net (code "103") (name "/DDR2.DQ61") (class "Default")
      (node (ref "U45") (pin "D9") (pinfunction "DQ13_D9") (pintype "bidirectional"))
    )
    (net (code "104") (name "/DDR2.DQ62") (class "Default")
      (node (ref "U45") (pin "B1") (pinfunction "DQ14_B1") (pintype "bidirectional"))
    )
    (net (code "105") (name "/DDR2.DQ63") (class "Default")
      (node (ref "U45") (pin "B9") (pinfunction "DQ15_B9") (pintype "bidirectional"))
    )
    (net (code "106") (name "/DDR2.DQS0") (class "Default")
      (node (ref "U42") (pin "F7") (pinfunction "LDQS_F7") (pintype "bidirectional"))
    )
    (net (code "107") (name "/DDR2.DQS1") (class "Default")
      (node (ref "U42") (pin "B7") (pinfunction "UDQS_B7") (pintype "bidirectional"))
    )
    (net (code "108") (name "/DDR2.DQS2") (class "Default")
      (node (ref "U43") (pin "F7") (pinfunction "LDQS_F7") (pintype "bidirectional"))
    )
    (net (code "109") (name "/DDR2.DQS3") (class "Default")
      (node (ref "U43") (pin "B7") (pinfunction "UDQS_B7") (pintype "bidirectional"))
    )
    (net (code "110") (name "/DDR2.DQS4") (class "Default")
      (node (ref "U44") (pin "F7") (pinfunction "LDQS_F7") (pintype "bidirectional"))
    )
    (net (code "111") (name "/DDR2.DQS5") (class "Default")
      (node (ref "U44") (pin "B7") (pinfunction "UDQS_B7") (pintype "bidirectional"))
    )
    (net (code "112") (name "/DDR2.DQS6") (class "Default")
      (node (ref "U45") (pin "F7") (pinfunction "LDQS_F7") (pintype "bidirectional"))
    )
    (net (code "113") (name "/DDR2.DQS7") (class "Default")
      (node (ref "U45") (pin "B7") (pinfunction "UDQS_B7") (pintype "bidirectional"))
    )
    (net (code "116") (name "/DDR2.ODT") (class "Default")
      (node (ref "U42") (pin "K9") (pinfunction "ODT_K9") (pintype "input"))
      (node (ref "U43") (pin "K9") (pinfunction "ODT_K9") (pintype "input"))
      (node (ref "U44") (pin "K9") (pinfunction "ODT_K9") (pintype "input"))
      (node (ref "U45") (pin "K9") (pinfunction "ODT_K9") (pintype "input"))
    )
    (net (code "117") (name "/DDR2.RASn") (class "Default")
      (node (ref "U42") (pin "K7") (pinfunction "RASn_K7") (pintype "input"))
      (node (ref "U43") (pin "K7") (pinfunction "RASn_K7") (pintype "input"))
      (node (ref "U44") (pin "K7") (pinfunction "RASn_K7") (pintype "input"))
      (node (ref "U45") (pin "K7") (pinfunction "RASn_K7") (pintype "input"))
    )
    (net (code "118") (name "/DDR2.Sn") (class "Default")
      (node (ref "U42") (pin "L8") (pinfunction "CSn_L8") (pintype "input"))
      (node (ref "U43") (pin "L8") (pinfunction "CSn_L8") (pintype "input"))
      (node (ref "U44") (pin "L8") (pinfunction "CSn_L8") (pintype "input"))
      (node (ref "U45") (pin "L8") (pinfunction "CSn_L8") (pintype "input"))
    )
    (net (code "119") (name "/DDR2.WEn") (class "Default")
      (node (ref "U42") (pin "K3") (pinfunction "WEn_K3") (pintype "input"))
      (node (ref "U43") (pin "K3") (pinfunction "WEn_K3") (pintype "input"))
      (node (ref "U44") (pin "K3") (pinfunction "WEn_K3") (pintype "input"))
      (node (ref "U45") (pin "K3") (pinfunction "WEn_K3") (pintype "input"))
    )
    (net (code "122") (name "1V8") (class "Default")
      (node (ref "C222") (pin "1") (pinfunction "1_1") (pintype "passive"))
      (node (ref "C224") (pin "2") (pinfunction "2_2") (pintype "passive"))
      (node (ref "C225") (pin "2") (pinfunction "2_2") (pintype "passive"))
      (node (ref "C226") (pin "2") (pinfunction "2_2") (pintype "passive"))
      (node (ref "C227") (pin "2") (pinfunction "2_2") (pintype "passive"))
      (node (ref "C228") (pin "2") (pinfunction "2_2") (pintype "passive"))
      (node (ref "C229") (pin "2") (pinfunction "2_2") (pintype "passive"))
      (node (ref "C230") (pin "2") (pinfunction "2_2") (pintype "passive"))
      (node (ref "C231") (pin "2") (pinfunction "2_2") (pintype "passive"))
      (node (ref "C232") (pin "1") (pinfunction "1_1") (pintype "passive"))
      (node (ref "C234") (pin "2") (pinfunction "2_2") (pintype "passive"))
      (node (ref "C235") (pin "2") (pinfunction "2_2") (pintype "passive"))
      (node (ref "C236") (pin "2") (pinfunction "2_2") (pintype "passive"))
      (node (ref "C237") (pin "2") (pinfunction "2_2") (pintype "passive"))
      (node (ref "C238") (pin "2") (pinfunction "2_2") (pintype "passive"))
      (node (ref "C239") (pin "2") (pinfunction "2_2") (pintype "passive"))
      (node (ref "C240") (pin "2") (pinfunction "2_2") (pintype "passive"))
      (node (ref "C241") (pin "2") (pinfunction "2_2") (pintype "passive"))
      (node (ref "C242") (pin "1") (pinfunction "1_1") (pintype "passive"))
      (node (ref "C244") (pin "2") (pinfunction "2_2") (pintype "passive"))
      (node (ref "C245") (pin "2") (pinfunction "2_2") (pintype "passive"))
      (node (ref "C246") (pin "2") (pinfunction "2_2") (pintype "passive"))
      (node (ref "C247") (pin "2") (pinfunction "2_2") (pintype "passive"))
      (node (ref "C248") (pin "2") (pinfunction "2_2") (pintype "passive"))
      (node (ref "C249") (pin "2") (pinfunction "2_2") (pintype "passive"))
      (node (ref "C250") (pin "2") (pinfunction "2_2") (pintype "passive"))
      (node (ref "C251") (pin "2") (pinfunction "2_2") (pintype "passive"))
      (node (ref "C252") (pin "1") (pinfunction "1_1") (pintype "passive"))
      (node (ref "C254") (pin "2") (pinfunction "2_2") (pintype "passive"))
      (node (ref "C255") (pin "2") (pinfunction "2_2") (pintype "passive"))
      (node (ref "C256") (pin "2") (pinfunction "2_2") (pintype "passive"))
      (node (ref "C257") (pin "2") (pinfunction "2_2") (pintype "passive"))
      (node (ref "C258") (pin "2") (pinfunction "2_2") (pintype "passive"))
      (node (ref "C259") (pin "2") (pinfunction "2_2") (pintype "passive"))
      (node (ref "C260") (pin "2") (pinfunction "2_2") (pintype "passive"))
      (node (ref "C261") (pin "2") (pinfunction "2_2") (pintype "passive"))
      (node (ref "C364") (pin "2") (pinfunction "2_2") (pintype "passive"))
      (node (ref "C372") (pin "2") (pinfunction "2_2") (pintype "passive"))
      (node (ref "C406") (pin "2") (pinfunction "2_2") (pintype "passive"))
      (node (ref "C407") (pin "2") (pinfunction "2_2") (pintype "passive"))
      (node (ref "U42") (pin "A1") (pinfunction "VDD_A1") (pintype "power_in"))
      (node (ref "U42") (pin "A9") (pinfunction "VDDQ_A9") (pintype "power_in"))
      (node (ref "U42") (pin "C1") (pinfunction "VDDQ_C1") (pintype "power_in"))
      (node (ref "U42") (pin "C3") (pinfunction "VDDQ_C3") (pintype "power_in"))
      (node (ref "U42") (pin "C7") (pinfunction "VDDQ_C7") (pintype "power_in"))
      (node (ref "U42") (pin "C9") (pinfunction "VDDQ_C9") (pintype "power_in"))
      (node (ref "U42") (pin "E1") (pinfunction "VDD_E1") (pintype "power_in"))
      (node (ref "U42") (pin "E9") (pinfunction "VDDQ_E9") (pintype "power_in"))
      (node (ref "U42") (pin "G1") (pinfunction "VDDQ_G1") (pintype "power_in"))
      (node (ref "U42") (pin "G3") (pinfunction "VDDQ_G3") (pintype "power_in"))
      (node (ref "U42") (pin "G7") (pinfunction "VDDQ_G7") (pintype "power_in"))
      (node (ref "U42") (pin "G9") (pinfunction "VDDQ_G9") (pintype "power_in"))
      (node (ref "U42") (pin "J1") (pinfunction "VDDL_J1") (pintype "power_in"))
      (node (ref "U42") (pin "J9") (pinfunction "VDD_J9") (pintype "power_in"))
      (node (ref "U42") (pin "M9") (pinfunction "VDD_M9") (pintype "power_in"))
      (node (ref "U42") (pin "R1") (pinfunction "VDD_R1") (pintype "power_in"))
      (node (ref "U43") (pin "A1") (pinfunction "VDD_A1") (pintype "power_in"))
      (node (ref "U43") (pin "A9") (pinfunction "VDDQ_A9") (pintype "power_in"))
      (node (ref "U43") (pin "C1") (pinfunction "VDDQ_C1") (pintype "power_in"))
      (node (ref "U43") (pin "C3") (pinfunction "VDDQ_C3") (pintype "power_in"))
      (node (ref "U43") (pin "C7") (pinfunction "VDDQ_C7") (pintype "power_in"))
      (node (ref "U43") (pin "C9") (pinfunction "VDDQ_C9") (pintype "power_in"))
      (node (ref "U43") (pin "E1") (pinfunction "VDD_E1") (pintype "power_in"))
      (node (ref "U43") (pin "E9") (pinfunction "VDDQ_E9") (pintype "power_in"))
      (node (ref "U43") (pin "G1") (pinfunction "VDDQ_G1") (pintype "power_in"))
      (node (ref "U43") (pin "G3") (pinfunction "VDDQ_G3") (pintype "power_in"))
      (node (ref "U43") (pin "G7") (pinfunction "VDDQ_G7") (pintype "power_in"))
      (node (ref "U43") (pin "G9") (pinfunction "VDDQ_G9") (pintype "power_in"))
      (node (ref "U43") (pin "J1") (pinfunction "VDDL_J1") (pintype "power_in"))
      (node (ref "U43") (pin "J9") (pinfunction "VDD_J9") (pintype "power_in"))
      (node (ref "U43") (pin "M9") (pinfunction "VDD_M9") (pintype "power_in"))
      (node (ref "U43") (pin "R1") (pinfunction "VDD_R1") (pintype "power_in"))
      (node (ref "U44") (pin "A1") (pinfunction "VDD_A1") (pintype "power_in"))
      (node (ref "U44") (pin "A9") (pinfunction "VDDQ_A9") (pintype "power_in"))
      (node (ref "U44") (pin "C1") (pinfunction "VDDQ_C1") (pintype "power_in"))
      (node (ref "U44") (pin "C3") (pinfunction "VDDQ_C3") (pintype "power_in"))
      (node (ref "U44") (pin "C7") (pinfunction "VDDQ_C7") (pintype "power_in"))
      (node (ref "U44") (pin "C9") (pinfunction "VDDQ_C9") (pintype "power_in"))
      (node (ref "U44") (pin "E1") (pinfunction "VDD_E1") (pintype "power_in"))
      (node (ref "U44") (pin "E9") (pinfunction "VDDQ_E9") (pintype "power_in"))
      (node (ref "U44") (pin "G1") (pinfunction "VDDQ_G1") (pintype "power_in"))
      (node (ref "U44") (pin "G3") (pinfunction "VDDQ_G3") (pintype "power_in"))
      (node (ref "U44") (pin "G7") (pinfunction "VDDQ_G7") (pintype "power_in"))
      (node (ref "U44") (pin "G9") (pinfunction "VDDQ_G9") (pintype "power_in"))
      (node (ref "U44") (pin "J1") (pinfunction "VDDL_J1") (pintype "power_in"))
      (node (ref "U44") (pin "J9") (pinfunction "VDD_J9") (pintype "power_in"))
      (node (ref "U44") (pin "M9") (pinfunction "VDD_M9") (pintype "power_in"))
      (node (ref "U44") (pin "R1") (pinfunction "VDD_R1") (pintype "power_in"))
      (node (ref "U45") (pin "A1") (pinfunction "VDD_A1") (pintype "power_in"))
      (node (ref "U45") (pin "A9") (pinfunction "VDDQ_A9") (pintype "power_in"))
      (node (ref "U45") (pin "C1") (pinfunction "VDDQ_C1") (pintype "power_in"))
      (node (ref "U45") (pin "C3") (pinfunction "VDDQ_C3") (pintype "power_in"))
      (node (ref "U45") (pin "C7") (pinfunction "VDDQ_C7") (pintype "power_in"))
      (node (ref "U45") (pin "C9") (pinfunction "VDDQ_C9") (pintype "power_in"))
      (node (ref "U45") (pin "E1") (pinfunction "VDD_E1") (pintype "power_in"))
      (node (ref "U45") (pin "E9") (pinfunction "VDDQ_E9") (pintype "power_in"))
      (node (ref "U45") (pin "G1") (pinfunction "VDDQ_G1") (pintype "power_in"))
      (node (ref "U45") (pin "G3") (pinfunction "VDDQ_G3") (pintype "power_in"))
      (node (ref "U45") (pin "G7") (pinfunction "VDDQ_G7") (pintype "power_in"))
      (node (ref "U45") (pin "G9") (pinfunction "VDDQ_G9") (pintype "power_in"))
      (node (ref "U45") (pin "J1") (pinfunction "VDDL_J1") (pintype "power_in"))
      (node (ref "U45") (pin "J9") (pinfunction "VDD_J9") (pintype "power_in"))
      (node (ref "U45") (pin "M9") (pinfunction "VDD_M9") (pintype "power_in"))
      (node (ref "U45") (pin "R1") (pinfunction "VDD_R1") (pintype "power_in"))
    )
    (net (code "123") (name "DDR2_VREF") (class "Default")
      (node (ref "C222") (pin "2") (pinfunction "2_2") (pintype "passive"))
      (node (ref "C223") (pin "2") (pinfunction "2_2") (pintype "passive"))
      (node (ref "C232") (pin "2") (pinfunction "2_2") (pintype "passive"))
      (node (ref "C233") (pin "2") (pinfunction "2_2") (pintype "passive"))
      (node (ref "C242") (pin "2") (pinfunction "2_2") (pintype "passive"))
      (node (ref "C243") (pin "2") (pinfunction "2_2") (pintype "passive"))
      (node (ref "C252") (pin "2") (pinfunction "2_2") (pintype "passive"))
      (node (ref "C253") (pin "2") (pinfunction "2_2") (pintype "passive"))
      (node (ref "U42") (pin "J2") (pinfunction "VREF_J2") (pintype "power_in"))
      (node (ref "U43") (pin "J2") (pinfunction "VREF_J2") (pintype "power_in"))
      (node (ref "U44") (pin "J2") (pinfunction "VREF_J2") (pintype "power_in"))
      (node (ref "U45") (pin "J2") (pinfunction "VREF_J2") (pintype "power_in"))
    )
    (net (code "124") (name "GND") (class "Default")
      (node (ref "C223") (pin "1") (pinfunction "1_1") (pintype "passive"))
      (node (ref "C224") (pin "1") (pinfunction "1_1") (pintype "passive"))
      (node (ref "C225") (pin "1") (pinfunction "1_1") (pintype "passive"))
      (node (ref "C226") (pin "1") (pinfunction "1_1") (pintype "passive"))
      (node (ref "C227") (pin "1") (pinfunction "1_1") (pintype "passive"))
      (node (ref "C228") (pin "1") (pinfunction "1_1") (pintype "passive"))
      (node (ref "C229") (pin "1") (pinfunction "1_1") (pintype "passive"))
      (node (ref "C230") (pin "1") (pinfunction "1_1") (pintype "passive"))
      (node (ref "C231") (pin "1") (pinfunction "1_1") (pintype "passive"))
      (node (ref "C233") (pin "1") (pinfunction "1_1") (pintype "passive"))
      (node (ref "C234") (pin "1") (pinfunction "1_1") (pintype "passive"))
      (node (ref "C235") (pin "1") (pinfunction "1_1") (pintype "passive"))
      (node (ref "C236") (pin "1") (pinfunction "1_1") (pintype "passive"))
      (node (ref "C237") (pin "1") (pinfunction "1_1") (pintype "passive"))
      (node (ref "C238") (pin "1") (pinfunction "1_1") (pintype "passive"))
      (node (ref "C239") (pin "1") (pinfunction "1_1") (pintype "passive"))
      (node (ref "C240") (pin "1") (pinfunction "1_1") (pintype "passive"))
      (node (ref "C241") (pin "1") (pinfunction "1_1") (pintype "passive"))
      (node (ref "C243") (pin "1") (pinfunction "1_1") (pintype "passive"))
      (node (ref "C244") (pin "1") (pinfunction "1_1") (pintype "passive"))
      (node (ref "C245") (pin "1") (pinfunction "1_1") (pintype "passive"))
      (node (ref "C246") (pin "1") (pinfunction "1_1") (pintype "passive"))
      (node (ref "C247") (pin "1") (pinfunction "1_1") (pintype "passive"))
      (node (ref "C248") (pin "1") (pinfunction "1_1") (pintype "passive"))
      (node (ref "C249") (pin "1") (pinfunction "1_1") (pintype "passive"))
      (node (ref "C250") (pin "1") (pinfunction "1_1") (pintype "passive"))
      (node (ref "C251") (pin "1") (pinfunction "1_1") (pintype "passive"))
      (node (ref "C253") (pin "1") (pinfunction "1_1") (pintype "passive"))
      (node (ref "C254") (pin "1") (pinfunction "1_1") (pintype "passive"))
      (node (ref "C255") (pin "1") (pinfunction "1_1") (pintype "passive"))
      (node (ref "C256") (pin "1") (pinfunction "1_1") (pintype "passive"))
      (node (ref "C257") (pin "1") (pinfunction "1_1") (pintype "passive"))
      (node (ref "C258") (pin "1") (pinfunction "1_1") (pintype "passive"))
      (node (ref "C259") (pin "1") (pinfunction "1_1") (pintype "passive"))
      (node (ref "C260") (pin "1") (pinfunction "1_1") (pintype "passive"))
      (node (ref "C261") (pin "1") (pinfunction "1_1") (pintype "passive"))
      (node (ref "C364") (pin "1") (pinfunction "1_1") (pintype "passive"))
      (node (ref "C372") (pin "1") (pinfunction "1_1") (pintype "passive"))
      (node (ref "C406") (pin "1") (pinfunction "1_1") (pintype "passive"))
      (node (ref "C407") (pin "1") (pinfunction "1_1") (pintype "passive"))
      (node (ref "U42") (pin "A3") (pinfunction "VSS_A3") (pintype "power_in"))
      (node (ref "U42") (pin "A7") (pinfunction "VSSQ_A7") (pintype "power_in"))
      (node (ref "U42") (pin "B2") (pinfunction "VSSQ_B2") (pintype "power_in"))
      (node (ref "U42") (pin "B8") (pinfunction "VSSQ_B8") (pintype "power_in"))
      (node (ref "U42") (pin "D2") (pinfunction "VSSQ_D2") (pintype "power_in"))
      (node (ref "U42") (pin "D8") (pinfunction "VSSQ_D8") (pintype "power_in"))
      (node (ref "U42") (pin "E3") (pinfunction "VSS_E3") (pintype "power_in"))
      (node (ref "U42") (pin "E7") (pinfunction "VSSQ_E7") (pintype "power_in"))
      (node (ref "U42") (pin "F2") (pinfunction "VSSQ_F2") (pintype "power_in"))
      (node (ref "U42") (pin "F8") (pinfunction "VSSQ_F8") (pintype "power_in"))
      (node (ref "U42") (pin "H2") (pinfunction "VSSQ_H2") (pintype "power_in"))
      (node (ref "U42") (pin "H8") (pinfunction "VSSQ_H8") (pintype "power_in"))
      (node (ref "U42") (pin "J3") (pinfunction "VSS_J3") (pintype "power_in"))
      (node (ref "U42") (pin "J7") (pinfunction "VSSDL_J7") (pintype "power_in"))
      (node (ref "U42") (pin "N1") (pinfunction "VSS_N1") (pintype "power_in"))
      (node (ref "U42") (pin "P9") (pinfunction "VSS_P9") (pintype "power_in"))
      (node (ref "U43") (pin "A3") (pinfunction "VSS_A3") (pintype "power_in"))
      (node (ref "U43") (pin "A7") (pinfunction "VSSQ_A7") (pintype "power_in"))
      (node (ref "U43") (pin "B2") (pinfunction "VSSQ_B2") (pintype "power_in"))
      (node (ref "U43") (pin "B8") (pinfunction "VSSQ_B8") (pintype "power_in"))
      (node (ref "U43") (pin "D2") (pinfunction "VSSQ_D2") (pintype "power_in"))
      (node (ref "U43") (pin "D8") (pinfunction "VSSQ_D8") (pintype "power_in"))
      (node (ref "U43") (pin "E3") (pinfunction "VSS_E3") (pintype "power_in"))
      (node (ref "U43") (pin "E7") (pinfunction "VSSQ_E7") (pintype "power_in"))
      (node (ref "U43") (pin "F2") (pinfunction "VSSQ_F2") (pintype "power_in"))
      (node (ref "U43") (pin "F8") (pinfunction "VSSQ_F8") (pintype "power_in"))
      (node (ref "U43") (pin "H2") (pinfunction "VSSQ_H2") (pintype "power_in"))
      (node (ref "U43") (pin "H8") (pinfunction "VSSQ_H8") (pintype "power_in"))
      (node (ref "U43") (pin "J3") (pinfunction "VSS_J3") (pintype "power_in"))
      (node (ref "U43") (pin "J7") (pinfunction "VSSDL_J7") (pintype "power_in"))
      (node (ref "U43") (pin "N1") (pinfunction "VSS_N1") (pintype "power_in"))
      (node (ref "U43") (pin "P9") (pinfunction "VSS_P9") (pintype "power_in"))
      (node (ref "U44") (pin "A3") (pinfunction "VSS_A3") (pintype "power_in"))
      (node (ref "U44") (pin "A7") (pinfunction "VSSQ_A7") (pintype "power_in"))
      (node (ref "U44") (pin "B2") (pinfunction "VSSQ_B2") (pintype "power_in"))
      (node (ref "U44") (pin "B8") (pinfunction "VSSQ_B8") (pintype "power_in"))
      (node (ref "U44") (pin "D2") (pinfunction "VSSQ_D2") (pintype "power_in"))
      (node (ref "U44") (pin "D8") (pinfunction "VSSQ_D8") (pintype "power_in"))
      (node (ref "U44") (pin "E3") (pinfunction "VSS_E3") (pintype "power_in"))
      (node (ref "U44") (pin "E7") (pinfunction "VSSQ_E7") (pintype "power_in"))
      (node (ref "U44") (pin "F2") (pinfunction "VSSQ_F2") (pintype "power_in"))
      (node (ref "U44") (pin "F8") (pinfunction "VSSQ_F8") (pintype "power_in"))
      (node (ref "U44") (pin "H2") (pinfunction "VSSQ_H2") (pintype "power_in"))
      (node (ref "U44") (pin "H8") (pinfunction "VSSQ_H8") (pintype "power_in"))
      (node (ref "U44") (pin "J3") (pinfunction "VSS_J3") (pintype "power_in"))
      (node (ref "U44") (pin "J7") (pinfunction "VSSDL_J7") (pintype "power_in"))
      (node (ref "U44") (pin "N1") (pinfunction "VSS_N1") (pintype "power_in"))
      (node (ref "U44") (pin "P9") (pinfunction "VSS_P9") (pintype "power_in"))
      (node (ref "U45") (pin "A3") (pinfunction "VSS_A3") (pintype "power_in"))
      (node (ref "U45") (pin "A7") (pinfunction "VSSQ_A7") (pintype "power_in"))
      (node (ref "U45") (pin "B2") (pinfunction "VSSQ_B2") (pintype "power_in"))
      (node (ref "U45") (pin "B8") (pinfunction "VSSQ_B8") (pintype "power_in"))
      (node (ref "U45") (pin "D2") (pinfunction "VSSQ_D2") (pintype "power_in"))
      (node (ref "U45") (pin "D8") (pinfunction "VSSQ_D8") (pintype "power_in"))
      (node (ref "U45") (pin "E3") (pinfunction "VSS_E3") (pintype "power_in"))
      (node (ref "U45") (pin "E7") (pinfunction "VSSQ_E7") (pintype "power_in"))
      (node (ref "U45") (pin "F2") (pinfunction "VSSQ_F2") (pintype "power_in"))
      (node (ref "U45") (pin "F8") (pinfunction "VSSQ_F8") (pintype "power_in"))
      (node (ref "U45") (pin "H2") (pinfunction "VSSQ_H2") (pintype "power_in"))
      (node (ref "U45") (pin "H8") (pinfunction "VSSQ_H8") (pintype "power_in"))
      (node (ref "U45") (pin "J3") (pinfunction "VSS_J3") (pintype "power_in"))
      (node (ref "U45") (pin "J7") (pinfunction "VSSDL_J7") (pintype "power_in"))
      (node (ref "U45") (pin "N1") (pinfunction "VSS_N1") (pintype "power_in"))
      (node (ref "U45") (pin "P9") (pinfunction "VSS_P9") (pintype "power_in"))
    )
    (net (code "125") (name "unconnected-(U42B-LDQSn-PadE8)") (class "Default")
      (node (ref "U42") (pin "E8") (pinfunction "LDQSn_E8") (pintype "bidirectional+no_connect"))
    )
    (net (code "126") (name "unconnected-(U42B-NC-PadA2)") (class "Default")
      (node (ref "U42") (pin "A2") (pinfunction "NC_A2") (pintype "passive+no_connect"))
    )
    (net (code "127") (name "unconnected-(U42B-NC-PadE2)") (class "Default")
      (node (ref "U42") (pin "E2") (pinfunction "NC_E2") (pintype "passive+no_connect"))
    )
    (net (code "128") (name "unconnected-(U42B-RFU-PadR3)") (class "Default")
      (node (ref "U42") (pin "R3") (pinfunction "RFU_R3") (pintype "passive+no_connect"))
    )
    (net (code "129") (name "unconnected-(U42B-RFU-PadR7)") (class "Default")
      (node (ref "U42") (pin "R7") (pinfunction "RFU_R7") (pintype "passive+no_connect"))
    )
    (net (code "130") (name "unconnected-(U42B-UDQSn-PadA8)") (class "Default")
      (node (ref "U42") (pin "A8") (pinfunction "UDQSn_A8") (pintype "bidirectional+no_connect"))
    )
    (net (code "131") (name "unconnected-(U43B-LDQSn-PadE8)") (class "Default")
      (node (ref "U43") (pin "E8") (pinfunction "LDQSn_E8") (pintype "bidirectional+no_connect"))
    )
    (net (code "132") (name "unconnected-(U43B-NC-PadA2)") (class "Default")
      (node (ref "U43") (pin "A2") (pinfunction "NC_A2") (pintype "passive+no_connect"))
    )
    (net (code "133") (name "unconnected-(U43B-NC-PadE2)") (class "Default")
      (node (ref "U43") (pin "E2") (pinfunction "NC_E2") (pintype "passive+no_connect"))
    )
    (net (code "134") (name "unconnected-(U43B-RFU-PadR3)") (class "Default")
      (node (ref "U43") (pin "R3") (pinfunction "RFU_R3") (pintype "passive+no_connect"))
    )
    (net (code "135") (name "unconnected-(U43B-RFU-PadR7)") (class "Default")
      (node (ref "U43") (pin "R7") (pinfunction "RFU_R7") (pintype "passive+no_connect"))
    )
    (net (code "136") (name "unconnected-(U43B-UDQSn-PadA8)") (class "Default")
      (node (ref "U43") (pin "A8") (pinfunction "UDQSn_A8") (pintype "bidirectional+no_connect"))
    )
    (net (code "137") (name "unconnected-(U44B-LDQSn-PadE8)") (class "Default")
      (node (ref "U44") (pin "E8") (pinfunction "LDQSn_E8") (pintype "bidirectional+no_connect"))
    )
    (net (code "138") (name "unconnected-(U44B-NC-PadA2)") (class "Default")
      (node (ref "U44") (pin "A2") (pinfunction "NC_A2") (pintype "passive+no_connect"))
    )
    (net (code "139") (name "unconnected-(U44B-NC-PadE2)") (class "Default")
      (node (ref "U44") (pin "E2") (pinfunction "NC_E2") (pintype "passive+no_connect"))
    )
    (net (code "140") (name "unconnected-(U44B-RFU-PadR3)") (class "Default")
      (node (ref "U44") (pin "R3") (pinfunction "RFU_R3") (pintype "passive+no_connect"))
    )
    (net (code "141") (name "unconnected-(U44B-RFU-PadR7)") (class "Default")
      (node (ref "U44") (pin "R7") (pinfunction "RFU_R7") (pintype "passive+no_connect"))
    )
    (net (code "142") (name "unconnected-(U44B-UDQSn-PadA8)") (class "Default")
      (node (ref "U44") (pin "A8") (pinfunction "UDQSn_A8") (pintype "bidirectional+no_connect"))
    )
    (net (code "143") (name "unconnected-(U45B-LDQSn-PadE8)") (class "Default")
      (node (ref "U45") (pin "E8") (pinfunction "LDQSn_E8") (pintype "bidirectional+no_connect"))
    )
    (net (code "144") (name "unconnected-(U45B-NC-PadA2)") (class "Default")
      (node (ref "U45") (pin "A2") (pinfunction "NC_A2") (pintype "passive+no_connect"))
    )
    (net (code "145") (name "unconnected-(U45B-NC-PadE2)") (class "Default")
      (node (ref "U45") (pin "E2") (pinfunction "NC_E2") (pintype "passive+no_connect"))
    )
    (net (code "146") (name "unconnected-(U45B-RFU-PadR3)") (class "Default")
      (node (ref "U45") (pin "R3") (pinfunction "RFU_R3") (pintype "passive+no_connect"))
    )
    (net (code "147") (name "unconnected-(U45B-RFU-PadR7)") (class "Default")
      (node (ref "U45") (pin "R7") (pinfunction "RFU_R7") (pintype "passive+no_connect"))
    )
    (net (code "148") (name "unconnected-(U45B-UDQSn-PadA8)") (class "Default")
      (node (ref "U45") (pin "A8") (pinfunction "UDQSn_A8") (pintype "bidirectional+no_connect"))
    )
  )
)
